# Prj_transboard_V2_0.net
KiCad netlist of a schematic drawn in EasyEDA Pro
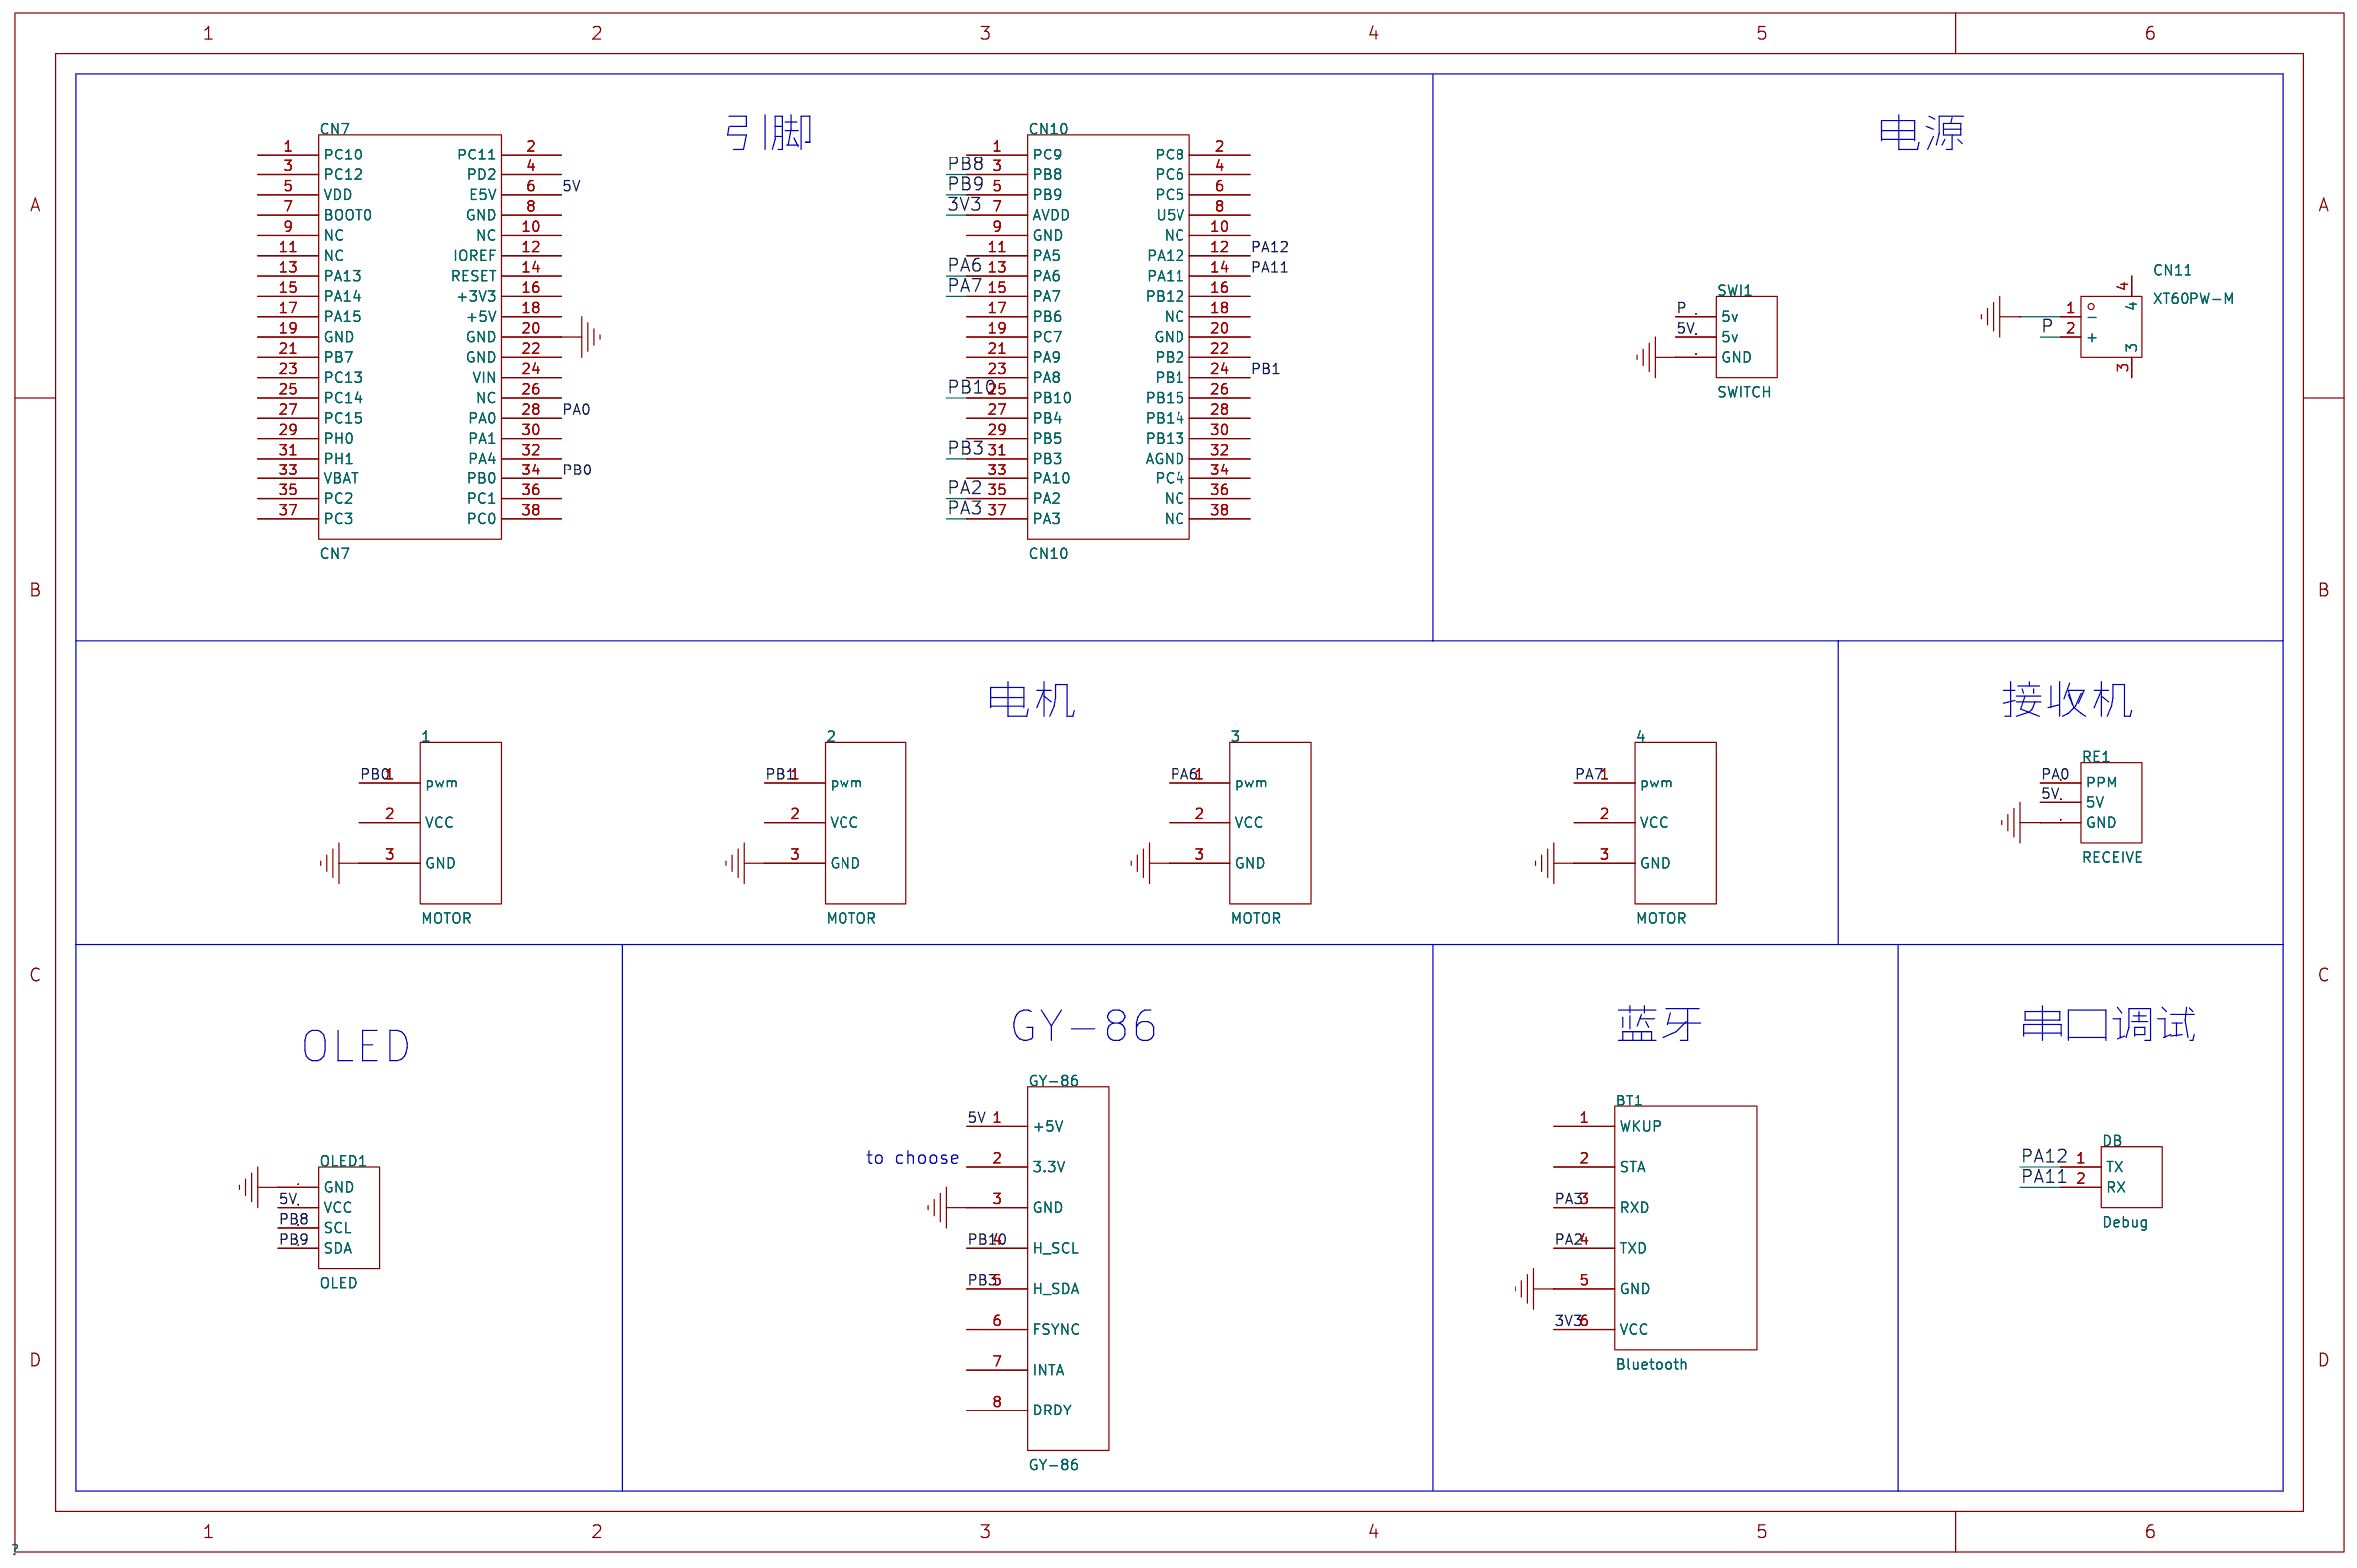
[diagram p0: schematic sheet]

(export (version "E")
  (design (tool "Eeschema 10.0.6"))
  (components
    (comp (ref "1") (value "MOTOR") (libsource (lib "easyedapro") (part "M")))
    (comp (ref "2") (value "MOTOR") (libsource (lib "easyedapro") (part "M")))
    (comp (ref "3") (value "MOTOR") (libsource (lib "easyedapro") (part "M")))
    (comp (ref "4") (value "MOTOR") (libsource (lib "easyedapro") (part "M")))
    (comp (ref "BT1") (value "Bluetooth") (libsource (lib "easyedapro") (part "Bluetooth")))
    (comp (ref "CN7") (value "CN7") (libsource (lib "easyedapro") (part "CN7")))
    (comp (ref "CN10") (value "CN10") (libsource (lib "easyedapro") (part "CN10")))
    (comp (ref "CN11")
      (value "XT60PW-M")
      (footprint "easyedapro:CONN-TH_XT60PW-M")
      (description "类别:-;类型1:-;")
      (fields (field (name "Manufacturer") "AMASS(艾迈斯)"))
      (libsource (lib "easyedapro") (part "XT60PW-M"))
    )
    (comp (ref "DB")
      (value "Debug")
      (description "Header, 2-Pin")
      (libsource (lib "easyedapro") (part "Header 2"))
    )
    (comp (ref "GY-86") (value "GY-86") (libsource (lib "easyedapro") (part "GY-86")))
    (comp (ref "OLED1")
      (value "OLED")
      (description "Header, 4-Pin")
      (libsource (lib "easyedapro") (part "Header 4"))
    )
    (comp (ref "RE1")
      (value "RECEIVE")
      (description "Header, 3-Pin")
      (libsource (lib "easyedapro") (part "Header 3"))
    )
    (comp (ref "SWI1")
      (value "SWITCH")
      (description "Header, 3-Pin")
      (libsource (lib "easyedapro") (part "Header 3_1"))
    )
  )
  (nets
    (net (code "1") (name "/3V3") (class "Default")
      (node (ref "BT1") (pin "6") (pinfunction "VCC_6") (pintype "unspecified"))
      (node (ref "CN10") (pin "7") (pinfunction "AVDD_7") (pintype "unspecified"))
    )
    (net (code "2") (name "/5V") (class "Default")
      (node (ref "CN7") (pin "6") (pinfunction "E5V_6") (pintype "unspecified"))
      (node (ref "GY-86") (pin "1") (pinfunction "+5V_1") (pintype "unspecified"))
      (node (ref "OLED1") (pin "2") (pinfunction "VCC_2") (pintype "unspecified"))
      (node (ref "RE1") (pin "2") (pinfunction "5V_2") (pintype "unspecified"))
      (node (ref "SWI1") (pin "2") (pinfunction "5v_2") (pintype "unspecified"))
    )
    (net (code "3") (name "/P") (class "Default")
      (node (ref "CN11") (pin "2") (pinfunction "+_2") (pintype "unspecified"))
      (node (ref "SWI1") (pin "1") (pinfunction "5v_1") (pintype "unspecified"))
    )
    (net (code "4") (name "/PA0") (class "Default")
      (node (ref "CN7") (pin "28") (pinfunction "PA0_28") (pintype "unspecified"))
      (node (ref "RE1") (pin "1") (pinfunction "PPM_1") (pintype "unspecified"))
    )
    (net (code "5") (name "/PA2") (class "Default")
      (node (ref "BT1") (pin "4") (pinfunction "TXD_4") (pintype "unspecified"))
      (node (ref "CN10") (pin "35") (pinfunction "PA2_35") (pintype "unspecified"))
    )
    (net (code "6") (name "/PA3") (class "Default")
      (node (ref "BT1") (pin "3") (pinfunction "RXD_3") (pintype "unspecified"))
      (node (ref "CN10") (pin "37") (pinfunction "PA3_37") (pintype "unspecified"))
    )
    (net (code "7") (name "/PA6") (class "Default")
      (node (ref "3") (pin "1") (pinfunction "pwm_1") (pintype "unspecified"))
      (node (ref "CN10") (pin "13") (pinfunction "PA6_13") (pintype "unspecified"))
    )
    (net (code "8") (name "/PA7") (class "Default")
      (node (ref "4") (pin "1") (pinfunction "pwm_1") (pintype "unspecified"))
      (node (ref "CN10") (pin "15") (pinfunction "PA7_15") (pintype "unspecified"))
    )
    (net (code "9") (name "/PA11") (class "Default")
      (node (ref "CN10") (pin "14") (pinfunction "PA11_14") (pintype "unspecified"))
      (node (ref "DB") (pin "2") (pinfunction "RX_2") (pintype "unspecified"))
    )
    (net (code "10") (name "/PA12") (class "Default")
      (node (ref "CN10") (pin "12") (pinfunction "PA12_12") (pintype "unspecified"))
      (node (ref "DB") (pin "1") (pinfunction "TX_1") (pintype "unspecified"))
    )
    (net (code "11") (name "/PB0") (class "Default")
      (node (ref "1") (pin "1") (pinfunction "pwm_1") (pintype "unspecified"))
      (node (ref "CN7") (pin "34") (pinfunction "PB0_34") (pintype "unspecified"))
    )
    (net (code "12") (name "/PB1") (class "Default")
      (node (ref "2") (pin "1") (pinfunction "pwm_1") (pintype "unspecified"))
      (node (ref "CN10") (pin "24") (pinfunction "PB1_24") (pintype "unspecified"))
    )
    (net (code "13") (name "/PB3") (class "Default")
      (node (ref "CN10") (pin "31") (pinfunction "PB3_31") (pintype "unspecified"))
      (node (ref "GY-86") (pin "5") (pinfunction "H_SDA_5") (pintype "unspecified"))
    )
    (net (code "14") (name "/PB8") (class "Default")
      (node (ref "CN10") (pin "3") (pinfunction "PB8_3") (pintype "unspecified"))
      (node (ref "OLED1") (pin "3") (pinfunction "SCL_3") (pintype "unspecified"))
    )
    (net (code "15") (name "/PB9") (class "Default")
      (node (ref "CN10") (pin "5") (pinfunction "PB9_5") (pintype "unspecified"))
      (node (ref "OLED1") (pin "4") (pinfunction "SDA_4") (pintype "unspecified"))
    )
    (net (code "16") (name "/PB10") (class "Default")
      (node (ref "CN10") (pin "25") (pinfunction "PB10_25") (pintype "unspecified"))
      (node (ref "GY-86") (pin "4") (pinfunction "H_SCL_4") (pintype "unspecified"))
    )
    (net (code "17") (name "GND") (class "Default")
      (node (ref "1") (pin "3") (pinfunction "GND_3") (pintype "unspecified"))
      (node (ref "2") (pin "3") (pinfunction "GND_3") (pintype "unspecified"))
      (node (ref "3") (pin "3") (pinfunction "GND_3") (pintype "unspecified"))
      (node (ref "4") (pin "3") (pinfunction "GND_3") (pintype "unspecified"))
      (node (ref "BT1") (pin "5") (pinfunction "GND_5") (pintype "unspecified"))
      (node (ref "CN11") (pin "1") (pinfunction "-_1") (pintype "unspecified"))
      (node (ref "CN7") (pin "20") (pinfunction "GND_20") (pintype "unspecified"))
      (node (ref "GY-86") (pin "3") (pinfunction "GND_3") (pintype "unspecified"))
      (node (ref "OLED1") (pin "1") (pinfunction "GND_1") (pintype "unspecified"))
      (node (ref "RE1") (pin "3") (pinfunction "GND_3") (pintype "unspecified"))
      (node (ref "SWI1") (pin "3") (pinfunction "GND_3") (pintype "unspecified"))
    )
    (net (code "18") (name "unconnected-(1-VCC-Pad2)") (class "Default")
      (node (ref "1") (pin "2") (pinfunction "VCC_2") (pintype "unspecified"))
    )
    (net (code "19") (name "unconnected-(2-VCC-Pad2)") (class "Default")
      (node (ref "2") (pin "2") (pinfunction "VCC_2") (pintype "unspecified"))
    )
    (net (code "20") (name "unconnected-(3-VCC-Pad2)") (class "Default")
      (node (ref "3") (pin "2") (pinfunction "VCC_2") (pintype "unspecified"))
    )
    (net (code "21") (name "unconnected-(4-VCC-Pad2)") (class "Default")
      (node (ref "4") (pin "2") (pinfunction "VCC_2") (pintype "unspecified"))
    )
    (net (code "22") (name "unconnected-(BT1-STA-Pad2)") (class "Default")
      (node (ref "BT1") (pin "2") (pinfunction "STA_2") (pintype "unspecified"))
    )
    (net (code "23") (name "unconnected-(BT1-WKUP-Pad1)") (class "Default")
      (node (ref "BT1") (pin "1") (pinfunction "WKUP_1") (pintype "unspecified"))
    )
    (net (code "24") (name "unconnected-(CN7-+3V3-Pad16)") (class "Default")
      (node (ref "CN7") (pin "16") (pinfunction "+3V3_16") (pintype "unspecified"))
    )
    (net (code "25") (name "unconnected-(CN7-+5V-Pad18)") (class "Default")
      (node (ref "CN7") (pin "18") (pinfunction "+5V_18") (pintype "unspecified"))
    )
    (net (code "26") (name "unconnected-(CN7-BOOT0-Pad7)") (class "Default")
      (node (ref "CN7") (pin "7") (pinfunction "BOOT0_7") (pintype "unspecified"))
    )
    (net (code "27") (name "unconnected-(CN7-GND-Pad8)") (class "Default")
      (node (ref "CN7") (pin "8") (pinfunction "GND_8") (pintype "unspecified"))
    )
    (net (code "28") (name "unconnected-(CN7-GND-Pad19)") (class "Default")
      (node (ref "CN7") (pin "19") (pinfunction "GND_19") (pintype "unspecified"))
    )
    (net (code "29") (name "unconnected-(CN7-GND-Pad22)") (class "Default")
      (node (ref "CN7") (pin "22") (pinfunction "GND_22") (pintype "unspecified"))
    )
    (net (code "30") (name "unconnected-(CN7-IOREF-Pad12)") (class "Default")
      (node (ref "CN7") (pin "12") (pinfunction "IOREF_12") (pintype "unspecified"))
    )
    (net (code "31") (name "unconnected-(CN7-NC-Pad9)") (class "Default")
      (node (ref "CN7") (pin "9") (pinfunction "NC_9") (pintype "unspecified"))
    )
    (net (code "32") (name "unconnected-(CN7-NC-Pad10)") (class "Default")
      (node (ref "CN7") (pin "10") (pinfunction "NC_10") (pintype "unspecified"))
    )
    (net (code "33") (name "unconnected-(CN7-NC-Pad11)") (class "Default")
      (node (ref "CN7") (pin "11") (pinfunction "NC_11") (pintype "unspecified"))
    )
    (net (code "34") (name "unconnected-(CN7-NC-Pad26)") (class "Default")
      (node (ref "CN7") (pin "26") (pinfunction "NC_26") (pintype "unspecified"))
    )
    (net (code "35") (name "unconnected-(CN7-PA1-Pad30)") (class "Default")
      (node (ref "CN7") (pin "30") (pinfunction "PA1_30") (pintype "unspecified"))
    )
    (net (code "36") (name "unconnected-(CN7-PA4-Pad32)") (class "Default")
      (node (ref "CN7") (pin "32") (pinfunction "PA4_32") (pintype "unspecified"))
    )
    (net (code "37") (name "unconnected-(CN7-PA13-Pad13)") (class "Default")
      (node (ref "CN7") (pin "13") (pinfunction "PA13_13") (pintype "unspecified"))
    )
    (net (code "38") (name "unconnected-(CN7-PA14-Pad15)") (class "Default")
      (node (ref "CN7") (pin "15") (pinfunction "PA14_15") (pintype "unspecified"))
    )
    (net (code "39") (name "unconnected-(CN7-PA15-Pad17)") (class "Default")
      (node (ref "CN7") (pin "17") (pinfunction "PA15_17") (pintype "unspecified"))
    )
    (net (code "40") (name "unconnected-(CN7-PB7-Pad21)") (class "Default")
      (node (ref "CN7") (pin "21") (pinfunction "PB7_21") (pintype "unspecified"))
    )
    (net (code "41") (name "unconnected-(CN7-PC0-Pad38)") (class "Default")
      (node (ref "CN7") (pin "38") (pinfunction "PC0_38") (pintype "unspecified"))
    )
    (net (code "42") (name "unconnected-(CN7-PC1-Pad36)") (class "Default")
      (node (ref "CN7") (pin "36") (pinfunction "PC1_36") (pintype "unspecified"))
    )
    (net (code "43") (name "unconnected-(CN7-PC2-Pad35)") (class "Default")
      (node (ref "CN7") (pin "35") (pinfunction "PC2_35") (pintype "unspecified"))
    )
    (net (code "44") (name "unconnected-(CN7-PC3-Pad37)") (class "Default")
      (node (ref "CN7") (pin "37") (pinfunction "PC3_37") (pintype "unspecified"))
    )
    (net (code "45") (name "unconnected-(CN7-PC10-Pad1)") (class "Default")
      (node (ref "CN7") (pin "1") (pinfunction "PC10_1") (pintype "unspecified"))
    )
    (net (code "46") (name "unconnected-(CN7-PC11-Pad2)") (class "Default")
      (node (ref "CN7") (pin "2") (pinfunction "PC11_2") (pintype "unspecified"))
    )
    (net (code "47") (name "unconnected-(CN7-PC12-Pad3)") (class "Default")
      (node (ref "CN7") (pin "3") (pinfunction "PC12_3") (pintype "unspecified"))
    )
    (net (code "48") (name "unconnected-(CN7-PC13-Pad23)") (class "Default")
      (node (ref "CN7") (pin "23") (pinfunction "PC13_23") (pintype "unspecified"))
    )
    (net (code "49") (name "unconnected-(CN7-PC14-Pad25)") (class "Default")
      (node (ref "CN7") (pin "25") (pinfunction "PC14_25") (pintype "unspecified"))
    )
    (net (code "50") (name "unconnected-(CN7-PC15-Pad27)") (class "Default")
      (node (ref "CN7") (pin "27") (pinfunction "PC15_27") (pintype "unspecified"))
    )
    (net (code "51") (name "unconnected-(CN7-PD2-Pad4)") (class "Default")
      (node (ref "CN7") (pin "4") (pinfunction "PD2_4") (pintype "unspecified"))
    )
    (net (code "52") (name "unconnected-(CN7-PH0-Pad29)") (class "Default")
      (node (ref "CN7") (pin "29") (pinfunction "PH0_29") (pintype "unspecified"))
    )
    (net (code "53") (name "unconnected-(CN7-PH1-Pad31)") (class "Default")
      (node (ref "CN7") (pin "31") (pinfunction "PH1_31") (pintype "unspecified"))
    )
    (net (code "54") (name "unconnected-(CN7-RESET-Pad14)") (class "Default")
      (node (ref "CN7") (pin "14") (pinfunction "RESET_14") (pintype "unspecified"))
    )
    (net (code "55") (name "unconnected-(CN7-VBAT-Pad33)") (class "Default")
      (node (ref "CN7") (pin "33") (pinfunction "VBAT_33") (pintype "unspecified"))
    )
    (net (code "56") (name "unconnected-(CN7-VDD-Pad5)") (class "Default")
      (node (ref "CN7") (pin "5") (pinfunction "VDD_5") (pintype "unspecified"))
    )
    (net (code "57") (name "unconnected-(CN7-VIN-Pad24)") (class "Default")
      (node (ref "CN7") (pin "24") (pinfunction "VIN_24") (pintype "unspecified"))
    )
    (net (code "58") (name "unconnected-(CN10-AGND-Pad32)") (class "Default")
      (node (ref "CN10") (pin "32") (pinfunction "AGND_32") (pintype "unspecified"))
    )
    (net (code "59") (name "unconnected-(CN10-GND-Pad9)") (class "Default")
      (node (ref "CN10") (pin "9") (pinfunction "GND_9") (pintype "unspecified"))
    )
    (net (code "60") (name "unconnected-(CN10-GND-Pad20)") (class "Default")
      (node (ref "CN10") (pin "20") (pinfunction "GND_20") (pintype "unspecified"))
    )
    (net (code "61") (name "unconnected-(CN10-NC-Pad10)") (class "Default")
      (node (ref "CN10") (pin "10") (pinfunction "NC_10") (pintype "unspecified"))
    )
    (net (code "62") (name "unconnected-(CN10-NC-Pad18)") (class "Default")
      (node (ref "CN10") (pin "18") (pinfunction "NC_18") (pintype "unspecified"))
    )
    (net (code "63") (name "unconnected-(CN10-NC-Pad36)") (class "Default")
      (node (ref "CN10") (pin "36") (pinfunction "NC_36") (pintype "unspecified"))
    )
    (net (code "64") (name "unconnected-(CN10-NC-Pad38)") (class "Default")
      (node (ref "CN10") (pin "38") (pinfunction "NC_38") (pintype "unspecified"))
    )
    (net (code "65") (name "unconnected-(CN10-PA5-Pad11)") (class "Default")
      (node (ref "CN10") (pin "11") (pinfunction "PA5_11") (pintype "unspecified"))
    )
    (net (code "66") (name "unconnected-(CN10-PA8-Pad23)") (class "Default")
      (node (ref "CN10") (pin "23") (pinfunction "PA8_23") (pintype "unspecified"))
    )
    (net (code "67") (name "unconnected-(CN10-PA9-Pad21)") (class "Default")
      (node (ref "CN10") (pin "21") (pinfunction "PA9_21") (pintype "unspecified"))
    )
    (net (code "68") (name "unconnected-(CN10-PA10-Pad33)") (class "Default")
      (node (ref "CN10") (pin "33") (pinfunction "PA10_33") (pintype "unspecified"))
    )
    (net (code "69") (name "unconnected-(CN10-PB2-Pad22)") (class "Default")
      (node (ref "CN10") (pin "22") (pinfunction "PB2_22") (pintype "unspecified"))
    )
    (net (code "70") (name "unconnected-(CN10-PB4-Pad27)") (class "Default")
      (node (ref "CN10") (pin "27") (pinfunction "PB4_27") (pintype "unspecified"))
    )
    (net (code "71") (name "unconnected-(CN10-PB5-Pad29)") (class "Default")
      (node (ref "CN10") (pin "29") (pinfunction "PB5_29") (pintype "unspecified"))
    )
    (net (code "72") (name "unconnected-(CN10-PB6-Pad17)") (class "Default")
      (node (ref "CN10") (pin "17") (pinfunction "PB6_17") (pintype "unspecified"))
    )
    (net (code "73") (name "unconnected-(CN10-PB12-Pad16)") (class "Default")
      (node (ref "CN10") (pin "16") (pinfunction "PB12_16") (pintype "unspecified"))
    )
    (net (code "74") (name "unconnected-(CN10-PB13-Pad30)") (class "Default")
      (node (ref "CN10") (pin "30") (pinfunction "PB13_30") (pintype "unspecified"))
    )
    (net (code "75") (name "unconnected-(CN10-PB14-Pad28)") (class "Default")
      (node (ref "CN10") (pin "28") (pinfunction "PB14_28") (pintype "unspecified"))
    )
    (net (code "76") (name "unconnected-(CN10-PB15-Pad26)") (class "Default")
      (node (ref "CN10") (pin "26") (pinfunction "PB15_26") (pintype "unspecified"))
    )
    (net (code "77") (name "unconnected-(CN10-PC4-Pad34)") (class "Default")
      (node (ref "CN10") (pin "34") (pinfunction "PC4_34") (pintype "unspecified"))
    )
    (net (code "78") (name "unconnected-(CN10-PC5-Pad6)") (class "Default")
      (node (ref "CN10") (pin "6") (pinfunction "PC5_6") (pintype "unspecified"))
    )
    (net (code "79") (name "unconnected-(CN10-PC6-Pad4)") (class "Default")
      (node (ref "CN10") (pin "4") (pinfunction "PC6_4") (pintype "unspecified"))
    )
    (net (code "80") (name "unconnected-(CN10-PC7-Pad19)") (class "Default")
      (node (ref "CN10") (pin "19") (pinfunction "PC7_19") (pintype "unspecified"))
    )
    (net (code "81") (name "unconnected-(CN10-PC8-Pad2)") (class "Default")
      (node (ref "CN10") (pin "2") (pinfunction "PC8_2") (pintype "unspecified"))
    )
    (net (code "82") (name "unconnected-(CN10-PC9-Pad1)") (class "Default")
      (node (ref "CN10") (pin "1") (pinfunction "PC9_1") (pintype "unspecified"))
    )
    (net (code "83") (name "unconnected-(CN10-U5V-Pad8)") (class "Default")
      (node (ref "CN10") (pin "8") (pinfunction "U5V_8") (pintype "unspecified"))
    )
    (net (code "84") (name "unconnected-(CN11-Pad3)") (class "Default")
      (node (ref "CN11") (pin "3") (pinfunction "3_3") (pintype "unspecified"))
    )
    (net (code "85") (name "unconnected-(CN11-Pad4)") (class "Default")
      (node (ref "CN11") (pin "4") (pinfunction "4_4") (pintype "unspecified"))
    )
    (net (code "86") (name "unconnected-(GY-86-3.3V-Pad2)") (class "Default")
      (node (ref "GY-86") (pin "2") (pinfunction "3.3V_2") (pintype "unspecified"))
    )
    (net (code "87") (name "unconnected-(GY-86-DRDY-Pad8)") (class "Default")
      (node (ref "GY-86") (pin "8") (pinfunction "DRDY_8") (pintype "unspecified"))
    )
    (net (code "88") (name "unconnected-(GY-86-FSYNC-Pad6)") (class "Default")
      (node (ref "GY-86") (pin "6") (pinfunction "FSYNC_6") (pintype "unspecified"))
    )
    (net (code "89") (name "unconnected-(GY-86-INTA-Pad7)") (class "Default")
      (node (ref "GY-86") (pin "7") (pinfunction "INTA_7") (pintype "unspecified"))
    )
  )
)
